# PCB.net
KiCad netlist of a schematic drawn in Altium Designer
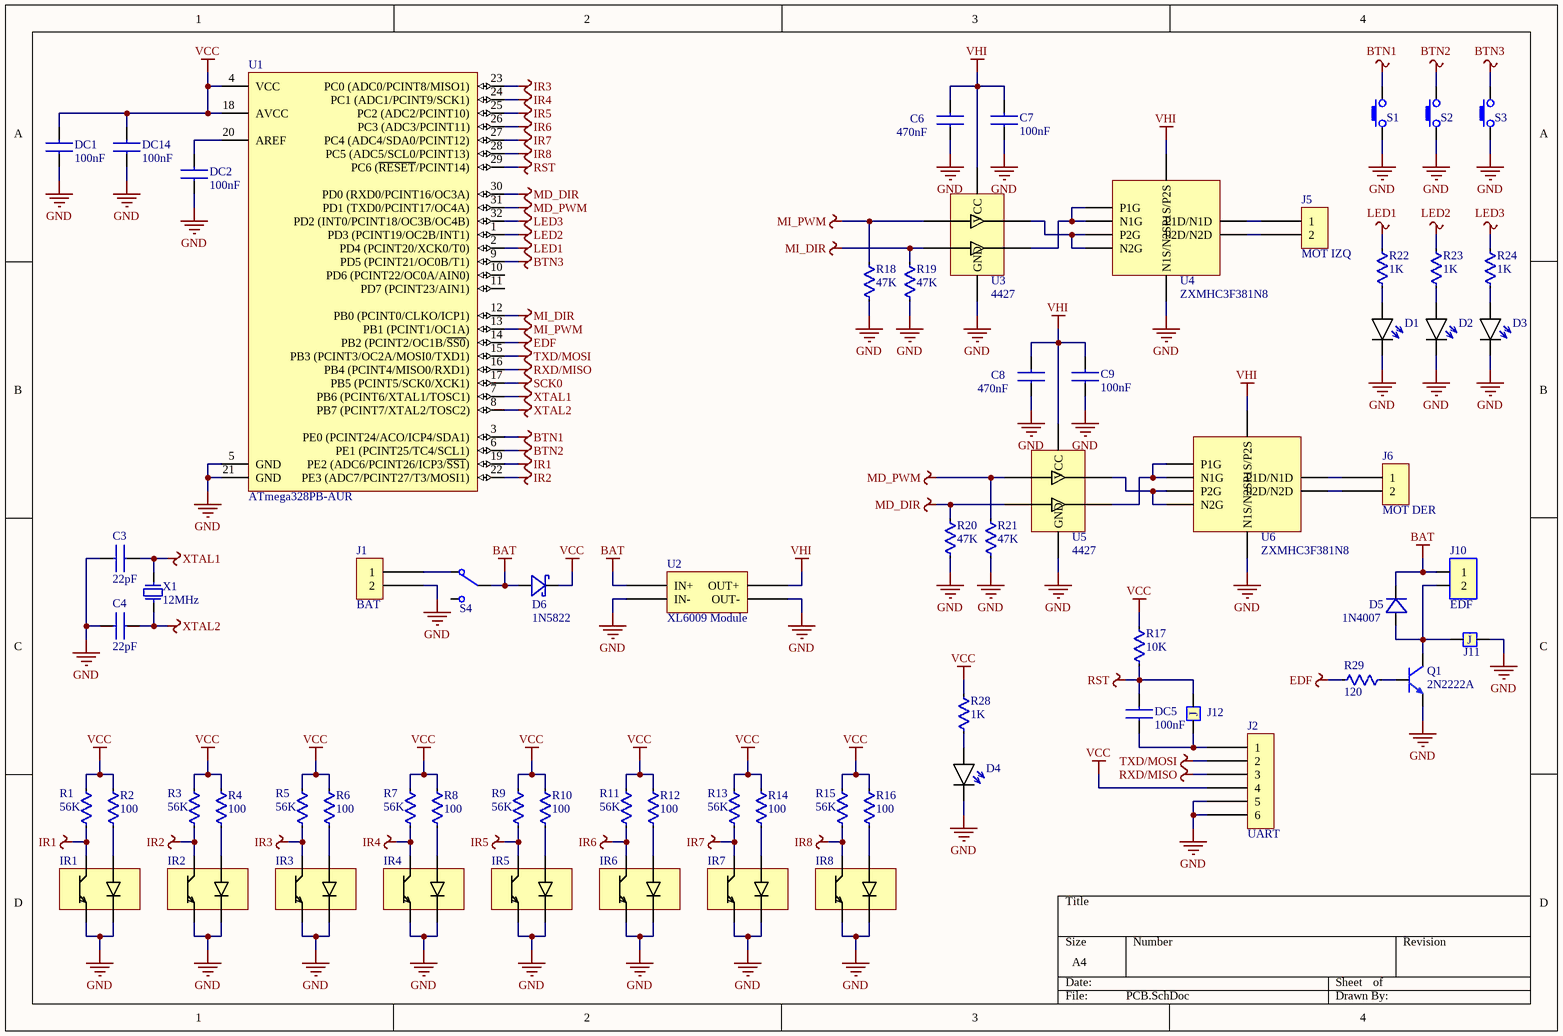
[diagram p0: PCB.SchDoc]

(export (version "E")
  (design (tool "Eeschema 10.0.6"))
  (components
    (comp (ref "C3")
      (value "22pF")
      (footprint "C1206")
      (fields (field (name "Comment") "CAP-CER"))
      (libsource (lib "AltiumLibrary") (part "CAP-CER"))
    )
    (comp (ref "C4")
      (value "22pF")
      (footprint "C1206")
      (fields (field (name "Comment") "CAP-CER"))
      (libsource (lib "AltiumLibrary") (part "CAP-CER"))
    )
    (comp (ref "C6")
      (value "470nF")
      (footprint "C1206")
      (fields (field (name "Comment") "CAP-CER"))
      (libsource (lib "AltiumLibrary") (part "CAP-CER"))
    )
    (comp (ref "C7")
      (value "100nF")
      (footprint "C1206")
      (fields (field (name "Comment") "CAP-CER"))
      (libsource (lib "AltiumLibrary") (part "CAP-CER"))
    )
    (comp (ref "C8")
      (value "470nF")
      (footprint "C1206")
      (fields (field (name "Comment") "CAP-CER"))
      (libsource (lib "AltiumLibrary") (part "CAP-CER"))
    )
    (comp (ref "C9")
      (value "100nF")
      (footprint "C1206")
      (fields (field (name "Comment") "CAP-CER"))
      (libsource (lib "AltiumLibrary") (part "CAP-CER"))
    )
    (comp (ref "D1")
      (value "LED")
      (footprint "LED-3MM-YELLOW")
      (libsource (lib "AltiumLibrary") (part "LED"))
    )
    (comp (ref "D2")
      (value "LED")
      (footprint "LED-3MM-YELLOW")
      (libsource (lib "AltiumLibrary") (part "LED"))
    )
    (comp (ref "D3")
      (value "LED")
      (footprint "LED-3MM-YELLOW")
      (libsource (lib "AltiumLibrary") (part "LED"))
    )
    (comp (ref "D4") (value "LED") (footprint "LED-3MM-RED") (libsource (lib "AltiumLibrary") (part "LED")))
    (comp (ref "D5")
      (value "DIODE")
      (footprint "DO-41")
      (fields (field (name "NAME") "1N4007"))
      (libsource (lib "AltiumLibrary") (part "DIODE"))
    )
    (comp (ref "D6") (value "1N5822") (footprint "DO-41") (libsource (lib "AltiumLibrary") (part "SCHOTTKY")))
    (comp (ref "DC1")
      (value "100nF")
      (footprint "C1206")
      (fields (field (name "Comment") "CAP-CER"))
      (libsource (lib "AltiumLibrary") (part "CAP-CER"))
    )
    (comp (ref "DC2")
      (value "100nF")
      (footprint "C1206")
      (fields (field (name "Comment") "CAP-CER"))
      (libsource (lib "AltiumLibrary") (part "CAP-CER"))
    )
    (comp (ref "DC5")
      (value "100nF")
      (footprint "C1206")
      (fields (field (name "Comment") "CAP-CER"))
      (libsource (lib "AltiumLibrary") (part "CAP-CER"))
    )
    (comp (ref "DC14")
      (value "100nF")
      (footprint "C1206")
      (fields (field (name "Comment") "CAP-CER"))
      (libsource (lib "AltiumLibrary") (part "CAP-CER"))
    )
    (comp (ref "IR1")
      (value "QRE1113GR")
      (footprint "QRE1113GR")
      (fields (field (name "MF") "ON Semiconductor"))
      (libsource (lib "AltiumLibrary") (part "QRE1113GR"))
    )
    (comp (ref "IR2")
      (value "QRE1113GR")
      (footprint "QRE1113GR")
      (fields (field (name "MF") "ON Semiconductor"))
      (libsource (lib "AltiumLibrary") (part "QRE1113GR"))
    )
    (comp (ref "IR3")
      (value "QRE1113GR")
      (footprint "QRE1113GR")
      (fields (field (name "MF") "ON Semiconductor"))
      (libsource (lib "AltiumLibrary") (part "QRE1113GR"))
    )
    (comp (ref "IR4")
      (value "QRE1113GR")
      (footprint "QRE1113GR")
      (fields (field (name "MF") "ON Semiconductor"))
      (libsource (lib "AltiumLibrary") (part "QRE1113GR"))
    )
    (comp (ref "IR5")
      (value "QRE1113GR")
      (footprint "QRE1113GR")
      (fields (field (name "MF") "ON Semiconductor"))
      (libsource (lib "AltiumLibrary") (part "QRE1113GR"))
    )
    (comp (ref "IR6")
      (value "QRE1113GR")
      (footprint "QRE1113GR")
      (fields (field (name "MF") "ON Semiconductor"))
      (libsource (lib "AltiumLibrary") (part "QRE1113GR"))
    )
    (comp (ref "IR7")
      (value "QRE1113GR")
      (footprint "QRE1113GR")
      (fields (field (name "MF") "ON Semiconductor"))
      (libsource (lib "AltiumLibrary") (part "QRE1113GR"))
    )
    (comp (ref "IR8")
      (value "QRE1113GR")
      (footprint "QRE1113GR")
      (fields (field (name "MF") "ON Semiconductor"))
      (libsource (lib "AltiumLibrary") (part "QRE1113GR"))
    )
    (comp (ref "J1")
      (value "BAT")
      (footprint "HEADER 1x2")
      (libsource (lib "AltiumLibrary") (part "Header 1x2"))
    )
    (comp (ref "J2")
      (value "UART")
      (footprint "Header 1x6")
      (libsource (lib "AltiumLibrary") (part "Header 1x6"))
    )
    (comp (ref "J5") (value "MOT IZQ") (footprint "HEADER 1x2") (libsource (lib "") (part "Header 1x2_1")))
    (comp (ref "J6") (value "MOT DER") (footprint "HEADER 1x2") (libsource (lib "") (part "Header 1x2_1")))
    (comp (ref "J10")
      (value "EDF")
      (footprint "BLOCK_TERMINAL-2")
      (libsource (lib "AltiumLibrary") (part "2-BLOCK_TERMINAL"))
    )
    (comp (ref "J11") (value "JUMPER") (footprint "JUMPER") (libsource (lib "") (part "JUMPER_1")))
    (comp (ref "J12") (value "JUMPER") (footprint "JUMPER") (libsource (lib "AltiumLibrary") (part "JUMPER")))
    (comp (ref "Q1") (value "2N2222A") (footprint "TO-92") (libsource (lib "AltiumLibrary") (part "NPN")))
    (comp (ref "R1")
      (value "56K")
      (footprint "R1206")
      (fields (field (name "Comment") "RES"))
      (libsource (lib "AltiumLibrary") (part "RES"))
    )
    (comp (ref "R2")
      (value "100")
      (footprint "R1206")
      (fields (field (name "Comment") "RES"))
      (libsource (lib "AltiumLibrary") (part "RES"))
    )
    (comp (ref "R3")
      (value "56K")
      (footprint "R1206")
      (fields (field (name "Comment") "RES"))
      (libsource (lib "AltiumLibrary") (part "RES"))
    )
    (comp (ref "R4")
      (value "100")
      (footprint "R1206")
      (fields (field (name "Comment") "RES"))
      (libsource (lib "AltiumLibrary") (part "RES"))
    )
    (comp (ref "R5")
      (value "56K")
      (footprint "R1206")
      (fields (field (name "Comment") "RES"))
      (libsource (lib "AltiumLibrary") (part "RES"))
    )
    (comp (ref "R6")
      (value "100")
      (footprint "R1206")
      (fields (field (name "Comment") "RES"))
      (libsource (lib "AltiumLibrary") (part "RES"))
    )
    (comp (ref "R7")
      (value "56K")
      (footprint "R1206")
      (fields (field (name "Comment") "RES"))
      (libsource (lib "AltiumLibrary") (part "RES"))
    )
    (comp (ref "R8")
      (value "100")
      (footprint "R1206")
      (fields (field (name "Comment") "RES"))
      (libsource (lib "AltiumLibrary") (part "RES"))
    )
    (comp (ref "R9")
      (value "56K")
      (footprint "R1206")
      (fields (field (name "Comment") "RES"))
      (libsource (lib "AltiumLibrary") (part "RES"))
    )
    (comp (ref "R10")
      (value "100")
      (footprint "R1206")
      (fields (field (name "Comment") "RES"))
      (libsource (lib "AltiumLibrary") (part "RES"))
    )
    (comp (ref "R11")
      (value "56K")
      (footprint "R1206")
      (fields (field (name "Comment") "RES"))
      (libsource (lib "AltiumLibrary") (part "RES"))
    )
    (comp (ref "R12")
      (value "100")
      (footprint "R1206")
      (fields (field (name "Comment") "RES"))
      (libsource (lib "AltiumLibrary") (part "RES"))
    )
    (comp (ref "R13")
      (value "56K")
      (footprint "R1206")
      (fields (field (name "Comment") "RES"))
      (libsource (lib "AltiumLibrary") (part "RES"))
    )
    (comp (ref "R14")
      (value "100")
      (footprint "R1206")
      (fields (field (name "Comment") "RES"))
      (libsource (lib "AltiumLibrary") (part "RES"))
    )
    (comp (ref "R15")
      (value "56K")
      (footprint "R1206")
      (fields (field (name "Comment") "RES"))
      (libsource (lib "AltiumLibrary") (part "RES"))
    )
    (comp (ref "R16")
      (value "100")
      (footprint "R1206")
      (fields (field (name "Comment") "RES"))
      (libsource (lib "AltiumLibrary") (part "RES"))
    )
    (comp (ref "R17")
      (value "10K")
      (footprint "R1206")
      (fields (field (name "Comment") "RES"))
      (libsource (lib "AltiumLibrary") (part "RES"))
    )
    (comp (ref "R18")
      (value "47K")
      (footprint "R1206")
      (fields (field (name "Comment") "RES"))
      (libsource (lib "AltiumLibrary") (part "RES"))
    )
    (comp (ref "R19")
      (value "47K")
      (footprint "R1206")
      (fields (field (name "Comment") "RES"))
      (libsource (lib "AltiumLibrary") (part "RES"))
    )
    (comp (ref "R20")
      (value "47K")
      (footprint "R1206")
      (fields (field (name "Comment") "RES"))
      (libsource (lib "AltiumLibrary") (part "RES"))
    )
    (comp (ref "R21")
      (value "47K")
      (footprint "R1206")
      (fields (field (name "Comment") "RES"))
      (libsource (lib "AltiumLibrary") (part "RES"))
    )
    (comp (ref "R22")
      (value "1K")
      (footprint "R1206")
      (fields (field (name "Comment") "RES"))
      (libsource (lib "AltiumLibrary") (part "RES"))
    )
    (comp (ref "R23")
      (value "1K")
      (footprint "R1206")
      (fields (field (name "Comment") "RES"))
      (libsource (lib "AltiumLibrary") (part "RES"))
    )
    (comp (ref "R24")
      (value "1K")
      (footprint "R1206")
      (fields (field (name "Comment") "RES"))
      (libsource (lib "AltiumLibrary") (part "RES"))
    )
    (comp (ref "R28")
      (value "1K")
      (footprint "R1206")
      (fields (field (name "Comment") "RES"))
      (libsource (lib "AltiumLibrary") (part "RES"))
    )
    (comp (ref "R29")
      (value "120")
      (footprint "R1206")
      (fields (field (name "Comment") "RES"))
      (libsource (lib "") (part "RES_1"))
    )
    (comp (ref "S1")
      (value "BUTTON")
      (footprint "TACT_SWITCH-SMALL-4PIN")
      (libsource (lib "AltiumLibrary") (part "BUTTON"))
    )
    (comp (ref "S2")
      (value "BUTTON")
      (footprint "TACT_SWITCH-SMALL-4PIN")
      (libsource (lib "AltiumLibrary") (part "BUTTON"))
    )
    (comp (ref "S3")
      (value "BUTTON")
      (footprint "TACT_SWITCH-SMALL-4PIN")
      (libsource (lib "AltiumLibrary") (part "BUTTON"))
    )
    (comp (ref "S4")
      (value "SLIDE-SWITCH")
      (footprint "SWITCH")
      (libsource (lib "AltiumLibrary") (part "SLIDE-SWITCH"))
    )
    (comp (ref "U1")
      (value "ATmega328PB-AUR")
      (footprint "32A_M")
      (libsource (lib "AltiumLibrary") (part "ATmega328PB-AUR"))
    )
    (comp (ref "U2")
      (value "XL6009 Module")
      (footprint "XL6009 mdl")
      (libsource (lib "AltiumLibrary") (part "XL6009 Module"))
    )
    (comp (ref "U3") (value "4427") (footprint "SOIC-8") (libsource (lib "AltiumLibrary") (part "4427")))
    (comp (ref "U4")
      (value "ZXMHC3F381N8")
      (footprint "SOIC-8")
      (libsource (lib "AltiumLibrary") (part "ZXMHC3F381N8"))
    )
    (comp (ref "U5") (value "4427") (footprint "SOIC-8") (libsource (lib "AltiumLibrary") (part "4427")))
    (comp (ref "U6")
      (value "ZXMHC3F381N8")
      (footprint "SOIC-8")
      (libsource (lib "AltiumLibrary") (part "ZXMHC3F381N8"))
    )
    (comp (ref "X1")
      (value "XTAL")
      (footprint "HC-49/S")
      (fields (field (name "FREQUENCY") "12MHz"))
      (libsource (lib "AltiumLibrary") (part "XTAL"))
    )
  )
  (nets
    (net (code "1") (name "BAT") (class "Default")
      (node (ref "D5") (pin "K") (pintype "passive"))
      (node (ref "D6") (pin "A") (pintype "passive"))
      (node (ref "J10") (pin "1") (pinfunction "1_1") (pintype "passive"))
      (node (ref "S4") (pin "2") (pintype "power_in"))
      (node (ref "U2") (pin "0") (pinfunction "IN+_0") (pintype "passive"))
    )
    (net (code "2") (name "BTN1") (class "Default")
      (node (ref "S1") (pin "2") (pintype "passive"))
      (node (ref "U1") (pin "3") (pinfunction "PE0_(PCINT24/ACO/ICP4/SDA1)_3") (pintype "bidirectional"))
    )
    (net (code "3") (name "BTN2") (class "Default")
      (node (ref "S2") (pin "2") (pintype "passive"))
      (node (ref "U1") (pin "6") (pinfunction "PE1_(PCINT25/TC4/SCL1)_6") (pintype "bidirectional"))
    )
    (net (code "4") (name "BTN3") (class "Default")
      (node (ref "S3") (pin "2") (pintype "passive"))
      (node (ref "U1") (pin "9") (pinfunction "PD5_(PCINT21/OC0B/T1)_9") (pintype "bidirectional"))
    )
    (net (code "5") (name "EDF") (class "Default")
      (node (ref "R29") (pin "1") (pintype "passive"))
      (node (ref "U1") (pin "14") (pinfunction "PB2_(PCINT2/OC1B/~{SS0})_14") (pintype "bidirectional"))
    )
    (net (code "6") (name "GND") (class "Default")
      (node (ref "C3") (pin "1") (pintype "passive"))
      (node (ref "C4") (pin "1") (pintype "passive"))
      (node (ref "C6") (pin "1") (pintype "passive"))
      (node (ref "C7") (pin "1") (pintype "passive"))
      (node (ref "C8") (pin "1") (pintype "passive"))
      (node (ref "C9") (pin "1") (pintype "passive"))
      (node (ref "D1") (pin "K") (pintype "passive"))
      (node (ref "D2") (pin "K") (pintype "passive"))
      (node (ref "D3") (pin "K") (pintype "passive"))
      (node (ref "D4") (pin "K") (pintype "passive"))
      (node (ref "DC1") (pin "2") (pintype "passive"))
      (node (ref "DC14") (pin "1") (pintype "passive"))
      (node (ref "DC2") (pin "2") (pintype "passive"))
      (node (ref "IR1") (pin "E") (pinfunction "E_E") (pintype "passive"))
      (node (ref "IR1") (pin "K") (pinfunction "K_K") (pintype "passive"))
      (node (ref "IR2") (pin "E") (pinfunction "E_E") (pintype "passive"))
      (node (ref "IR2") (pin "K") (pinfunction "K_K") (pintype "passive"))
      (node (ref "IR3") (pin "E") (pinfunction "E_E") (pintype "passive"))
      (node (ref "IR3") (pin "K") (pinfunction "K_K") (pintype "passive"))
      (node (ref "IR4") (pin "E") (pinfunction "E_E") (pintype "passive"))
      (node (ref "IR4") (pin "K") (pinfunction "K_K") (pintype "passive"))
      (node (ref "IR5") (pin "E") (pinfunction "E_E") (pintype "passive"))
      (node (ref "IR5") (pin "K") (pinfunction "K_K") (pintype "passive"))
      (node (ref "IR6") (pin "E") (pinfunction "E_E") (pintype "passive"))
      (node (ref "IR6") (pin "K") (pinfunction "K_K") (pintype "passive"))
      (node (ref "IR7") (pin "E") (pinfunction "E_E") (pintype "passive"))
      (node (ref "IR7") (pin "K") (pinfunction "K_K") (pintype "passive"))
      (node (ref "IR8") (pin "E") (pinfunction "E_E") (pintype "passive"))
      (node (ref "IR8") (pin "K") (pinfunction "K_K") (pintype "passive"))
      (node (ref "J1") (pin "2") (pinfunction "2_2") (pintype "passive"))
      (node (ref "J11") (pin "1") (pintype "passive"))
      (node (ref "J2") (pin "5") (pinfunction "5_5") (pintype "passive"))
      (node (ref "J2") (pin "6") (pinfunction "6_6") (pintype "passive"))
      (node (ref "Q1") (pin "E") (pinfunction "E_E") (pintype "passive"))
      (node (ref "R18") (pin "1") (pintype "passive"))
      (node (ref "R19") (pin "1") (pintype "passive"))
      (node (ref "R20") (pin "1") (pintype "passive"))
      (node (ref "R21") (pin "1") (pintype "passive"))
      (node (ref "S1") (pin "1") (pintype "passive"))
      (node (ref "S2") (pin "1") (pintype "passive"))
      (node (ref "S3") (pin "1") (pintype "passive"))
      (node (ref "U1") (pin "21") (pinfunction "GND_21") (pintype "power_in"))
      (node (ref "U1") (pin "5") (pinfunction "GND_5") (pintype "power_in"))
      (node (ref "U2") (pin "1") (pinfunction "IN-_1") (pintype "passive"))
      (node (ref "U2") (pin "2") (pinfunction "OUT-_2") (pintype "passive"))
      (node (ref "U3") (pin "3") (pinfunction "GND_3") (pintype "passive"))
      (node (ref "U4") (pin "3") (pinfunction "N1S/N2S_3") (pintype "passive"))
      (node (ref "U5") (pin "3") (pinfunction "GND_3") (pintype "passive"))
      (node (ref "U6") (pin "3") (pinfunction "N1S/N2S_3") (pintype "passive"))
    )
    (net (code "7") (name "IR1") (class "Default")
      (node (ref "IR1") (pin "C") (pinfunction "C_C") (pintype "passive"))
      (node (ref "R1") (pin "1") (pintype "passive"))
      (node (ref "U1") (pin "19") (pinfunction "PE2_(ADC6/PCINT26/ICP3/~{SS1})_19") (pintype "bidirectional"))
    )
    (net (code "8") (name "IR2") (class "Default")
      (node (ref "IR2") (pin "C") (pinfunction "C_C") (pintype "passive"))
      (node (ref "R3") (pin "1") (pintype "passive"))
      (node (ref "U1") (pin "22") (pinfunction "PE3_(ADC7/PCINT27/T3/MOSI1)_22") (pintype "bidirectional"))
    )
    (net (code "9") (name "IR3") (class "Default")
      (node (ref "IR3") (pin "C") (pinfunction "C_C") (pintype "passive"))
      (node (ref "R5") (pin "1") (pintype "passive"))
      (node (ref "U1") (pin "23") (pinfunction "PC0_(ADC0/PCINT8/MISO1)_23") (pintype "bidirectional"))
    )
    (net (code "10") (name "IR4") (class "Default")
      (node (ref "IR4") (pin "C") (pinfunction "C_C") (pintype "passive"))
      (node (ref "R7") (pin "1") (pintype "passive"))
      (node (ref "U1") (pin "24") (pinfunction "PC1_(ADC1/PCINT9/SCK1)_24") (pintype "bidirectional"))
    )
    (net (code "11") (name "IR5") (class "Default")
      (node (ref "IR5") (pin "C") (pinfunction "C_C") (pintype "passive"))
      (node (ref "R9") (pin "1") (pintype "passive"))
      (node (ref "U1") (pin "25") (pinfunction "PC2_(ADC2/PCINT10)_25") (pintype "bidirectional"))
    )
    (net (code "12") (name "IR6") (class "Default")
      (node (ref "IR6") (pin "C") (pinfunction "C_C") (pintype "passive"))
      (node (ref "R11") (pin "1") (pintype "passive"))
      (node (ref "U1") (pin "26") (pinfunction "PC3_(ADC3/PCINT11)_26") (pintype "bidirectional"))
    )
    (net (code "13") (name "IR7") (class "Default")
      (node (ref "IR7") (pin "C") (pinfunction "C_C") (pintype "passive"))
      (node (ref "R13") (pin "1") (pintype "passive"))
      (node (ref "U1") (pin "27") (pinfunction "PC4_(ADC4/SDA0/PCINT12)_27") (pintype "bidirectional"))
    )
    (net (code "14") (name "IR8") (class "Default")
      (node (ref "IR8") (pin "C") (pinfunction "C_C") (pintype "passive"))
      (node (ref "R15") (pin "1") (pintype "passive"))
      (node (ref "U1") (pin "28") (pinfunction "PC5_(ADC5/SCL0/PCINT13)_28") (pintype "bidirectional"))
    )
    (net (code "15") (name "LED1") (class "Default")
      (node (ref "R22") (pin "2") (pintype "passive"))
      (node (ref "U1") (pin "2") (pinfunction "PD4_(PCINT20/XCK0/T0)_2") (pintype "bidirectional"))
    )
    (net (code "16") (name "LED2") (class "Default")
      (node (ref "R23") (pin "2") (pintype "passive"))
      (node (ref "U1") (pin "1") (pinfunction "PD3_(PCINT19/OC2B/INT1)_1") (pintype "bidirectional"))
    )
    (net (code "17") (name "LED3") (class "Default")
      (node (ref "R24") (pin "2") (pintype "passive"))
      (node (ref "U1") (pin "32") (pinfunction "PD2_(INT0/PCINT18/OC3B/OC4B)_32") (pintype "bidirectional"))
    )
    (net (code "18") (name "MD_DIR") (class "Default")
      (node (ref "R20") (pin "2") (pintype "passive"))
      (node (ref "U1") (pin "30") (pinfunction "PD0_(RXD0/PCINT16/OC3A)_30") (pintype "bidirectional"))
      (node (ref "U5") (pin "4") (pinfunction "INB_4") (pintype "passive"))
    )
    (net (code "19") (name "MD_PWM") (class "Default")
      (node (ref "R21") (pin "2") (pintype "passive"))
      (node (ref "U1") (pin "31") (pinfunction "PD1_(TXD0/PCINT17/OC4A)_31") (pintype "bidirectional"))
      (node (ref "U5") (pin "2") (pinfunction "INA_2") (pintype "passive"))
    )
    (net (code "20") (name "MI_DIR") (class "Default")
      (node (ref "R19") (pin "2") (pintype "passive"))
      (node (ref "U1") (pin "12") (pinfunction "PB0_(PCINT0/CLKO/ICP1)_12") (pintype "bidirectional"))
      (node (ref "U3") (pin "4") (pinfunction "INB_4") (pintype "passive"))
    )
    (net (code "21") (name "MI_PWM") (class "Default")
      (node (ref "R18") (pin "2") (pintype "passive"))
      (node (ref "U1") (pin "13") (pinfunction "PB1_(PCINT1/OC1A)_13") (pintype "bidirectional"))
      (node (ref "U3") (pin "2") (pinfunction "INA_2") (pintype "passive"))
    )
    (net (code "22") (name "Net-(D1-PadA)") (class "Default")
      (node (ref "D1") (pin "A") (pintype "passive"))
      (node (ref "R22") (pin "1") (pintype "passive"))
    )
    (net (code "23") (name "Net-(D2-PadA)") (class "Default")
      (node (ref "D2") (pin "A") (pintype "passive"))
      (node (ref "R23") (pin "1") (pintype "passive"))
    )
    (net (code "24") (name "Net-(D3-PadA)") (class "Default")
      (node (ref "D3") (pin "A") (pintype "passive"))
      (node (ref "R24") (pin "1") (pintype "passive"))
    )
    (net (code "25") (name "Net-(D4-PadA)") (class "Default")
      (node (ref "D4") (pin "A") (pintype "passive"))
      (node (ref "R28") (pin "1") (pintype "passive"))
    )
    (net (code "26") (name "Net-(D5-PadA)") (class "Default")
      (node (ref "D5") (pin "A") (pintype "passive"))
      (node (ref "J10") (pin "2") (pinfunction "2_2") (pintype "passive"))
      (node (ref "J11") (pin "2") (pintype "passive"))
      (node (ref "Q1") (pin "C") (pinfunction "C_C") (pintype "passive"))
    )
    (net (code "27") (name "Net-(DC5-Pad2)") (class "Default")
      (node (ref "DC5") (pin "2") (pintype "passive"))
      (node (ref "J12") (pin "2") (pintype "passive"))
      (node (ref "J2") (pin "1") (pinfunction "1_1") (pintype "passive"))
    )
    (net (code "28") (name "Net-(IR1-PadA)") (class "Default")
      (node (ref "IR1") (pin "A") (pinfunction "A_A") (pintype "passive"))
      (node (ref "R2") (pin "1") (pintype "passive"))
    )
    (net (code "29") (name "Net-(IR2-PadA)") (class "Default")
      (node (ref "IR2") (pin "A") (pinfunction "A_A") (pintype "passive"))
      (node (ref "R4") (pin "1") (pintype "passive"))
    )
    (net (code "30") (name "Net-(IR3-PadA)") (class "Default")
      (node (ref "IR3") (pin "A") (pinfunction "A_A") (pintype "passive"))
      (node (ref "R6") (pin "1") (pintype "passive"))
    )
    (net (code "31") (name "Net-(IR4-PadA)") (class "Default")
      (node (ref "IR4") (pin "A") (pinfunction "A_A") (pintype "passive"))
      (node (ref "R8") (pin "1") (pintype "passive"))
    )
    (net (code "32") (name "Net-(IR5-PadA)") (class "Default")
      (node (ref "IR5") (pin "A") (pinfunction "A_A") (pintype "passive"))
      (node (ref "R10") (pin "1") (pintype "passive"))
    )
    (net (code "33") (name "Net-(IR6-PadA)") (class "Default")
      (node (ref "IR6") (pin "A") (pinfunction "A_A") (pintype "passive"))
      (node (ref "R12") (pin "1") (pintype "passive"))
    )
    (net (code "34") (name "Net-(IR7-PadA)") (class "Default")
      (node (ref "IR7") (pin "A") (pinfunction "A_A") (pintype "passive"))
      (node (ref "R14") (pin "1") (pintype "passive"))
    )
    (net (code "35") (name "Net-(IR8-PadA)") (class "Default")
      (node (ref "IR8") (pin "A") (pinfunction "A_A") (pintype "passive"))
      (node (ref "R16") (pin "1") (pintype "passive"))
    )
    (net (code "36") (name "Net-(J1-Pad1)") (class "Default")
      (node (ref "J1") (pin "1") (pinfunction "1_1") (pintype "passive"))
      (node (ref "S4") (pin "1") (pintype "power_in"))
    )
    (net (code "37") (name "Net-(Q1-PadB)") (class "Default")
      (node (ref "Q1") (pin "B") (pinfunction "B_B") (pintype "passive"))
      (node (ref "R29") (pin "2") (pintype "passive"))
    )
    (net (code "38") (name "Net-(U1-AREF)") (class "Default")
      (node (ref "DC2") (pin "1") (pintype "passive"))
      (node (ref "U1") (pin "20") (pinfunction "AREF_20") (pintype "passive"))
    )
    (net (code "39") (name "Net-(U3-OUTA)") (class "Default")
      (node (ref "U3") (pin "7") (pinfunction "OUTA_7") (pintype "passive"))
      (node (ref "U4") (pin "4") (pinfunction "N2G_4") (pintype "passive"))
      (node (ref "U4") (pin "5") (pinfunction "P2G_5") (pintype "passive"))
    )
    (net (code "40") (name "Net-(U3-OUTB)") (class "Default")
      (node (ref "U3") (pin "5") (pinfunction "OUTB_5") (pintype "passive"))
      (node (ref "U4") (pin "1") (pinfunction "N1G_1") (pintype "passive"))
      (node (ref "U4") (pin "8") (pinfunction "P1G_8") (pintype "passive"))
    )
    (net (code "41") (name "Net-(U4-P1D{slash}N1D)") (class "Default")
      (node (ref "J5") (pin "1") (pinfunction "1_1") (pintype "passive"))
      (node (ref "U4") (pin "2") (pinfunction "P1D/N1D_2") (pintype "passive"))
    )
    (net (code "42") (name "Net-(U4-P2D{slash}N2D)") (class "Default")
      (node (ref "J5") (pin "2") (pinfunction "2_2") (pintype "passive"))
      (node (ref "U4") (pin "6") (pinfunction "P2D/N2D_6") (pintype "passive"))
    )
    (net (code "43") (name "Net-(U5-OUTA)") (class "Default")
      (node (ref "U5") (pin "7") (pinfunction "OUTA_7") (pintype "passive"))
      (node (ref "U6") (pin "4") (pinfunction "N2G_4") (pintype "passive"))
      (node (ref "U6") (pin "5") (pinfunction "P2G_5") (pintype "passive"))
    )
    (net (code "44") (name "Net-(U5-OUTB)") (class "Default")
      (node (ref "U5") (pin "5") (pinfunction "OUTB_5") (pintype "passive"))
      (node (ref "U6") (pin "1") (pinfunction "N1G_1") (pintype "passive"))
      (node (ref "U6") (pin "8") (pinfunction "P1G_8") (pintype "passive"))
    )
    (net (code "45") (name "Net-(U6-P1D{slash}N1D)") (class "Default")
      (node (ref "J6") (pin "1") (pinfunction "1_1") (pintype "passive"))
      (node (ref "U6") (pin "2") (pinfunction "P1D/N1D_2") (pintype "passive"))
    )
    (net (code "46") (name "Net-(U6-P2D{slash}N2D)") (class "Default")
      (node (ref "J6") (pin "2") (pinfunction "2_2") (pintype "passive"))
      (node (ref "U6") (pin "6") (pinfunction "P2D/N2D_6") (pintype "passive"))
    )
    (net (code "47") (name "RST") (class "Default")
      (node (ref "DC5") (pin "1") (pintype "passive"))
      (node (ref "J12") (pin "1") (pintype "passive"))
      (node (ref "R17") (pin "1") (pintype "passive"))
      (node (ref "U1") (pin "29") (pinfunction "PC6_(~{RESET}/PCINT14)_29") (pintype "bidirectional"))
    )
    (net (code "48") (name "RXD{slash}MISO") (class "Default")
      (node (ref "J2") (pin "3") (pinfunction "3_3") (pintype "passive"))
      (node (ref "U1") (pin "16") (pinfunction "PB4_(PCINT4/MISO0/RXD1)_16") (pintype "bidirectional"))
    )
    (net (code "49") (name "SCK0") (class "Default")
      (node (ref "U1") (pin "17") (pinfunction "PB5_(PCINT5/SCK0/XCK1)_17") (pintype "bidirectional"))
    )
    (net (code "50") (name "TXD{slash}MOSI") (class "Default")
      (node (ref "J2") (pin "2") (pinfunction "2_2") (pintype "passive"))
      (node (ref "U1") (pin "15") (pinfunction "PB3_(PCINT3/OC2A/MOSI0/TXD1)_15") (pintype "bidirectional"))
    )
    (net (code "51") (name "VCC") (class "Default")
      (node (ref "D6") (pin "K") (pintype "passive"))
      (node (ref "DC1") (pin "1") (pintype "passive"))
      (node (ref "DC14") (pin "2") (pintype "passive"))
      (node (ref "J2") (pin "4") (pinfunction "4_4") (pintype "passive"))
      (node (ref "R1") (pin "2") (pintype "passive"))
      (node (ref "R10") (pin "2") (pintype "passive"))
      (node (ref "R11") (pin "2") (pintype "passive"))
      (node (ref "R12") (pin "2") (pintype "passive"))
      (node (ref "R13") (pin "2") (pintype "passive"))
      (node (ref "R14") (pin "2") (pintype "passive"))
      (node (ref "R15") (pin "2") (pintype "passive"))
      (node (ref "R16") (pin "2") (pintype "passive"))
      (node (ref "R17") (pin "2") (pintype "passive"))
      (node (ref "R2") (pin "2") (pintype "passive"))
      (node (ref "R28") (pin "2") (pintype "passive"))
      (node (ref "R3") (pin "2") (pintype "passive"))
      (node (ref "R4") (pin "2") (pintype "passive"))
      (node (ref "R5") (pin "2") (pintype "passive"))
      (node (ref "R6") (pin "2") (pintype "passive"))
      (node (ref "R7") (pin "2") (pintype "passive"))
      (node (ref "R8") (pin "2") (pintype "passive"))
      (node (ref "R9") (pin "2") (pintype "passive"))
      (node (ref "U1") (pin "18") (pinfunction "AVCC_18") (pintype "power_in"))
      (node (ref "U1") (pin "4") (pinfunction "VCC_4") (pintype "power_in"))
    )
    (net (code "52") (name "VHI") (class "Default")
      (node (ref "C6") (pin "2") (pintype "passive"))
      (node (ref "C7") (pin "2") (pintype "passive"))
      (node (ref "C8") (pin "2") (pintype "passive"))
      (node (ref "C9") (pin "2") (pintype "passive"))
      (node (ref "U2") (pin "3") (pinfunction "OUT+_3") (pintype "passive"))
      (node (ref "U3") (pin "6") (pinfunction "VCC_6") (pintype "passive"))
      (node (ref "U4") (pin "7") (pinfunction "P1S/P2S_7") (pintype "passive"))
      (node (ref "U5") (pin "6") (pinfunction "VCC_6") (pintype "passive"))
      (node (ref "U6") (pin "7") (pinfunction "P1S/P2S_7") (pintype "passive"))
    )
    (net (code "53") (name "XTAL1") (class "Default")
      (node (ref "C3") (pin "2") (pintype "passive"))
      (node (ref "U1") (pin "7") (pinfunction "PB6_(PCINT6/XTAL1/TOSC1)_7") (pintype "bidirectional"))
      (node (ref "X1") (pin "2") (pintype "passive"))
    )
    (net (code "54") (name "XTAL2") (class "Default")
      (node (ref "C4") (pin "2") (pintype "passive"))
      (node (ref "U1") (pin "8") (pinfunction "PB7_(PCINT7/XTAL2/TOSC2)_8") (pintype "bidirectional"))
      (node (ref "X1") (pin "1") (pintype "passive"))
    )
    (net (code "55") (name "unconnected-(S4-Pad3)") (class "Default")
      (node (ref "S4") (pin "3") (pintype "power_in"))
    )
    (net (code "56") (name "unconnected-(U1-PD6_(PCINT22{slash}OC0A{slash}AIN0)-Pad10)") (class "Default")
      (node (ref "U1") (pin "10") (pinfunction "PD6_(PCINT22/OC0A/AIN0)_10") (pintype "bidirectional"))
    )
    (net (code "57") (name "unconnected-(U1-PD7_(PCINT23{slash}AIN1)-Pad11)") (class "Default")
      (node (ref "U1") (pin "11") (pinfunction "PD7_(PCINT23/AIN1)_11") (pintype "bidirectional"))
    )
  )
)
